# PIC.net
KiCad netlist of a schematic drawn in Altium Designer
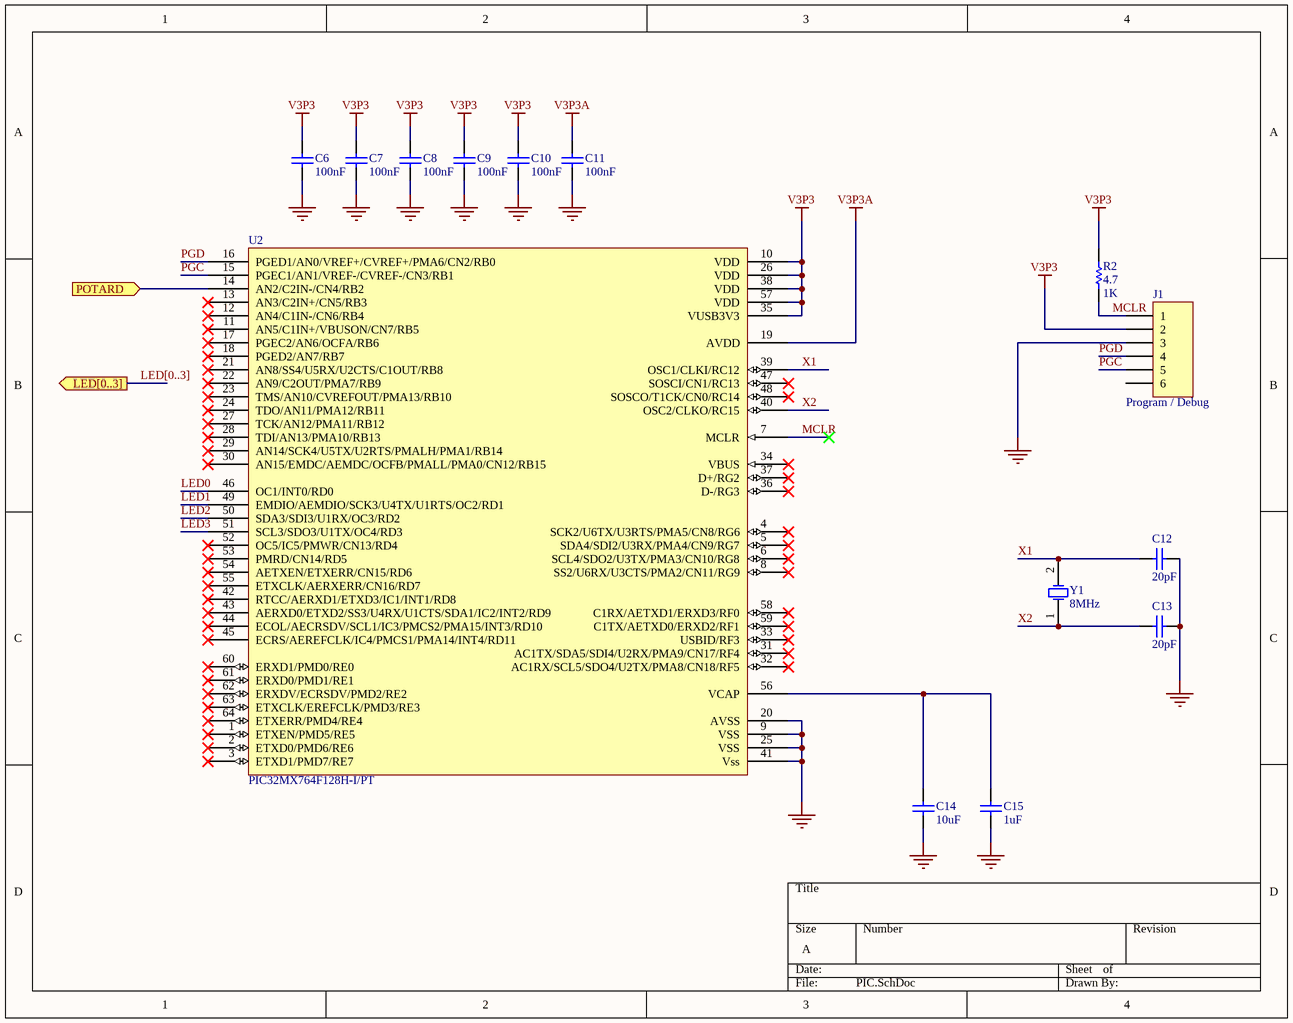
[diagram p0: PIC.SchDoc]

(export (version "E")
  (design (tool "Eeschema 10.0.6"))
  (components
    (comp (ref "C6")
      (value "100nF")
      (footprint "CAPC1608N")
      (description "Capacitor")
      (fields (field (name "PUBLISHER") "Altium Limited"))
      (libsource (lib "Miscellaneous Devices") (part "Cap"))
    )
    (comp (ref "C7")
      (value "100nF")
      (footprint "CAPC1608N")
      (description "Capacitor")
      (fields (field (name "PUBLISHER") "Altium Limited"))
      (libsource (lib "Miscellaneous Devices") (part "Cap"))
    )
    (comp (ref "C8")
      (value "100nF")
      (footprint "CAPC1608N")
      (description "Capacitor")
      (fields (field (name "PUBLISHER") "Altium Limited"))
      (libsource (lib "Miscellaneous Devices") (part "Cap"))
    )
    (comp (ref "C9")
      (value "100nF")
      (footprint "CAPC2012N")
      (description "Capacitor")
      (fields (field (name "PUBLISHER") "Altium Limited"))
      (libsource (lib "Miscellaneous Devices") (part "Cap"))
    )
    (comp (ref "C10")
      (value "100nF")
      (footprint "CAPC1608N")
      (description "Capacitor")
      (fields (field (name "PUBLISHER") "Altium Limited"))
      (libsource (lib "Miscellaneous Devices") (part "Cap"))
    )
    (comp (ref "C11")
      (value "100nF")
      (footprint "CAPC2012N")
      (description "Capacitor")
      (fields (field (name "PUBLISHER") "Altium Limited"))
      (libsource (lib "Miscellaneous Devices") (part "Cap"))
    )
    (comp (ref "C12")
      (value "20pF")
      (footprint "CAPC2012N")
      (description "Capacitor")
      (fields (field (name "PUBLISHER") "Altium Limited"))
      (libsource (lib "Miscellaneous Devices") (part "Cap"))
    )
    (comp (ref "C13")
      (value "20pF")
      (footprint "CAPC2012N")
      (description "Capacitor")
      (fields (field (name "PUBLISHER") "Altium Limited"))
      (libsource (lib "Miscellaneous Devices") (part "Cap"))
    )
    (comp (ref "C14")
      (value "10uF")
      (footprint "CAPC1608N")
      (description "Capacitor")
      (fields (field (name "PUBLISHER") "Altium Limited"))
      (libsource (lib "Miscellaneous Devices") (part "Cap"))
    )
    (comp (ref "C15")
      (value "1uF")
      (footprint "CAPC1608N")
      (description "Capacitor")
      (fields (field (name "PUBLISHER") "Altium Limited"))
      (libsource (lib "Miscellaneous Devices") (part "Cap"))
    )
    (comp (ref "J1")
      (value "Program / Debug")
      (footprint "RJ12_90")
      (description "Header, 6-Pin")
      (fields (field (name "PUBLISHER") "Altium Limited"))
      (libsource (lib "Miscellaneous Connectors") (part "Header 6"))
    )
    (comp (ref "R2")
      (value "4.7")
      (footprint "RESC1608N")
      (description "Resistor")
      (fields (field (name "ALTIUM_VALUE") "1K") (field (name "PUBLISHER") "Altium Limited"))
      (libsource (lib "Miscellaneous Devices") (part "Res1"))
    )
    (comp (ref "U2")
      (value "PIC32MX764F128H-I/PT")
      (footprint "QFP50P1200X1200X120-64")
      (libsource (lib "tp2") (part "PIC32MX764F128H-I/PT"))
    )
    (comp (ref "Y1")
      (value "8MHz")
      (footprint "HC49/4H SMX CRYSTAL")
      (description "Crystal Oscillator")
      (fields (field (name "PUBLISHER") "Altium Limited"))
      (libsource (lib "Miscellaneous Devices") (part "XTAL"))
    )
  )
  (nets
    (net (code "1") (name "/LED0") (class "Default")
      (node (ref "U2") (pin "46") (pinfunction "OC1/INT0/RD0_46") (pintype "passive"))
    )
    (net (code "2") (name "/LED1") (class "Default")
      (node (ref "U2") (pin "49") (pinfunction "EMDIO/AEMDIO/SCK3/U4TX/U1RTS/OC2/RD1_49") (pintype "passive"))
    )
    (net (code "3") (name "/LED2") (class "Default")
      (node (ref "U2") (pin "50") (pinfunction "SDA3/SDI3/U1RX/OC3/RD2_50") (pintype "passive"))
    )
    (net (code "4") (name "/LED3") (class "Default")
      (node (ref "U2") (pin "51") (pinfunction "SCL3/SDO3/U1TX/OC4/RD3_51") (pintype "passive"))
    )
    (net (code "6") (name "/MCLR") (class "Default")
      (node (ref "J1") (pin "1") (pinfunction "1_1") (pintype "passive"))
      (node (ref "R2") (pin "1") (pinfunction "1_1") (pintype "passive"))
      (node (ref "U2") (pin "7") (pinfunction "MCLR_7") (pintype "input"))
    )
    (net (code "7") (name "/PGC") (class "Default")
      (node (ref "J1") (pin "5") (pinfunction "5_5") (pintype "passive"))
      (node (ref "U2") (pin "15") (pinfunction "PGEC1/AN1/VREF-/CVREF-/CN3/RB1_15") (pintype "passive"))
    )
    (net (code "8") (name "/PGD") (class "Default")
      (node (ref "J1") (pin "4") (pinfunction "4_4") (pintype "passive"))
      (node (ref "U2") (pin "16") (pinfunction "PGED1/AN0/VREF+/CVREF+/PMA6/CN2/RB0_16") (pintype "passive"))
    )
    (net (code "9") (name "/POTARD") (class "Default")
      (node (ref "U2") (pin "14") (pinfunction "AN2/C2IN-/CN4/RB2_14") (pintype "passive"))
    )
    (net (code "10") (name "/X1") (class "Default")
      (node (ref "C12") (pin "2") (pinfunction "2_2") (pintype "passive"))
      (node (ref "U2") (pin "39") (pinfunction "OSC1/CLKI/RC12_39") (pintype "bidirectional"))
      (node (ref "Y1") (pin "2") (pinfunction "OSC2_2") (pintype "passive"))
    )
    (net (code "11") (name "/X2") (class "Default")
      (node (ref "C13") (pin "2") (pinfunction "2_2") (pintype "passive"))
      (node (ref "U2") (pin "40") (pinfunction "OSC2/CLKO/RC15_40") (pintype "bidirectional"))
      (node (ref "Y1") (pin "1") (pinfunction "OSC1_1") (pintype "passive"))
    )
    (net (code "12") (name "GND") (class "Default")
      (node (ref "C10") (pin "1") (pinfunction "1_1") (pintype "passive"))
      (node (ref "C11") (pin "1") (pinfunction "1_1") (pintype "passive"))
      (node (ref "C12") (pin "1") (pinfunction "1_1") (pintype "passive"))
      (node (ref "C13") (pin "1") (pinfunction "1_1") (pintype "passive"))
      (node (ref "C14") (pin "1") (pinfunction "1_1") (pintype "passive"))
      (node (ref "C15") (pin "1") (pinfunction "1_1") (pintype "passive"))
      (node (ref "C6") (pin "1") (pinfunction "1_1") (pintype "passive"))
      (node (ref "C7") (pin "1") (pinfunction "1_1") (pintype "passive"))
      (node (ref "C8") (pin "1") (pinfunction "1_1") (pintype "passive"))
      (node (ref "C9") (pin "1") (pinfunction "1_1") (pintype "passive"))
      (node (ref "J1") (pin "3") (pinfunction "3_3") (pintype "passive"))
      (node (ref "U2") (pin "20") (pinfunction "AVSS_20") (pintype "power_in"))
      (node (ref "U2") (pin "25") (pinfunction "VSS_25") (pintype "power_in"))
      (node (ref "U2") (pin "41") (pinfunction "Vss_41") (pintype "power_in"))
      (node (ref "U2") (pin "9") (pinfunction "VSS_9") (pintype "power_in"))
    )
    (net (code "13") (name "Net-(U2-VCAP)") (class "Default")
      (node (ref "C14") (pin "2") (pinfunction "2_2") (pintype "passive"))
      (node (ref "C15") (pin "2") (pinfunction "2_2") (pintype "passive"))
      (node (ref "U2") (pin "56") (pinfunction "VCAP_56") (pintype "power_in"))
    )
    (net (code "14") (name "V3P3") (class "Default")
      (node (ref "C10") (pin "2") (pinfunction "2_2") (pintype "passive"))
      (node (ref "C6") (pin "2") (pinfunction "2_2") (pintype "passive"))
      (node (ref "C7") (pin "2") (pinfunction "2_2") (pintype "passive"))
      (node (ref "C8") (pin "2") (pinfunction "2_2") (pintype "passive"))
      (node (ref "C9") (pin "2") (pinfunction "2_2") (pintype "passive"))
      (node (ref "J1") (pin "2") (pinfunction "2_2") (pintype "passive"))
      (node (ref "R2") (pin "2") (pinfunction "2_2") (pintype "passive"))
      (node (ref "U2") (pin "10") (pinfunction "VDD_10") (pintype "power_in"))
      (node (ref "U2") (pin "26") (pinfunction "VDD_26") (pintype "power_in"))
      (node (ref "U2") (pin "35") (pinfunction "VUSB3V3_35") (pintype "power_in"))
      (node (ref "U2") (pin "38") (pinfunction "VDD_38") (pintype "power_in"))
      (node (ref "U2") (pin "57") (pinfunction "VDD_57") (pintype "power_in"))
    )
    (net (code "15") (name "V3P3A") (class "Default")
      (node (ref "C11") (pin "2") (pinfunction "2_2") (pintype "passive"))
      (node (ref "U2") (pin "19") (pinfunction "AVDD_19") (pintype "power_in"))
    )
    (net (code "16") (name "unconnected-(J1-Pad6)") (class "Default")
      (node (ref "J1") (pin "6") (pinfunction "6_6") (pintype "passive"))
    )
    (net (code "17") (name "unconnected-(U2-AC1RX{slash}SCL5{slash}SDO4{slash}U2TX{slash}PMA8{slash}CN18{slash}RF5-Pad32)") (class "Default")
      (node (ref "U2") (pin "32") (pinfunction "AC1RX/SCL5/SDO4/U2TX/PMA8/CN18/RF5_32") (pintype "bidirectional+no_connect"))
    )
    (net (code "18") (name "unconnected-(U2-AC1TX{slash}SDA5{slash}SDI4{slash}U2RX{slash}PMA9{slash}CN17{slash}RF4-Pad31)") (class "Default")
      (node (ref "U2") (pin "31") (pinfunction "AC1TX/SDA5/SDI4/U2RX/PMA9/CN17/RF4_31") (pintype "bidirectional+no_connect"))
    )
    (net (code "19") (name "unconnected-(U2-AERXD0{slash}ETXD2{slash}SS3{slash}U4RX{slash}U1CTS{slash}SDA1{slash}IC2{slash}INT2{slash}RD9-Pad43)") (class "Default")
      (node (ref "U2") (pin "43") (pinfunction "AERXD0/ETXD2/SS3/U4RX/U1CTS/SDA1/IC2/INT2/RD9_43") (pintype "passive+no_connect"))
    )
    (net (code "20") (name "unconnected-(U2-AETXEN{slash}ETXERR{slash}CN15{slash}RD6-Pad54)") (class "Default")
      (node (ref "U2") (pin "54") (pinfunction "AETXEN/ETXERR/CN15/RD6_54") (pintype "passive+no_connect"))
    )
    (net (code "21") (name "unconnected-(U2-AN3{slash}C2IN+{slash}CN5{slash}RB3-Pad13)") (class "Default")
      (node (ref "U2") (pin "13") (pinfunction "AN3/C2IN+/CN5/RB3_13") (pintype "passive+no_connect"))
    )
    (net (code "22") (name "unconnected-(U2-AN4{slash}C1IN-{slash}CN6{slash}RB4-Pad12)") (class "Default")
      (node (ref "U2") (pin "12") (pinfunction "AN4/C1IN-/CN6/RB4_12") (pintype "passive+no_connect"))
    )
    (net (code "23") (name "unconnected-(U2-AN5{slash}C1IN+{slash}VBUSON{slash}CN7{slash}RB5-Pad11)") (class "Default")
      (node (ref "U2") (pin "11") (pinfunction "AN5/C1IN+/VBUSON/CN7/RB5_11") (pintype "passive+no_connect"))
    )
    (net (code "24") (name "unconnected-(U2-AN8{slash}SS4{slash}U5RX{slash}U2CTS{slash}C1OUT{slash}RB8-Pad21)") (class "Default")
      (node (ref "U2") (pin "21") (pinfunction "AN8/SS4/U5RX/U2CTS/C1OUT/RB8_21") (pintype "passive+no_connect"))
    )
    (net (code "25") (name "unconnected-(U2-AN9{slash}C2OUT{slash}PMA7{slash}RB9-Pad22)") (class "Default")
      (node (ref "U2") (pin "22") (pinfunction "AN9/C2OUT/PMA7/RB9_22") (pintype "passive+no_connect"))
    )
    (net (code "26") (name "unconnected-(U2-AN14{slash}SCK4{slash}U5TX{slash}U2RTS{slash}PMALH{slash}PMA1{slash}RB14-Pad29)") (class "Default")
      (node (ref "U2") (pin "29") (pinfunction "AN14/SCK4/U5TX/U2RTS/PMALH/PMA1/RB14_29") (pintype "passive+no_connect"))
    )
    (net (code "27") (name "unconnected-(U2-AN15{slash}EMDC{slash}AEMDC{slash}OCFB{slash}PMALL{slash}PMA0{slash}CN12{slash}RB15-Pad30)") (class "Default")
      (node (ref "U2") (pin "30") (pinfunction "AN15/EMDC/AEMDC/OCFB/PMALL/PMA0/CN12/RB15_30") (pintype "passive+no_connect"))
    )
    (net (code "28") (name "unconnected-(U2-C1RX{slash}AETXD1{slash}ERXD3{slash}RF0-Pad58)") (class "Default")
      (node (ref "U2") (pin "58") (pinfunction "C1RX/AETXD1/ERXD3/RF0_58") (pintype "bidirectional+no_connect"))
    )
    (net (code "29") (name "unconnected-(U2-C1TX{slash}AETXD0{slash}ERXD2{slash}RF1-Pad59)") (class "Default")
      (node (ref "U2") (pin "59") (pinfunction "C1TX/AETXD0/ERXD2/RF1_59") (pintype "bidirectional+no_connect"))
    )
    (net (code "30") (name "unconnected-(U2-D+{slash}RG2-Pad37)") (class "Default")
      (node (ref "U2") (pin "37") (pinfunction "D+/RG2_37") (pintype "bidirectional+no_connect"))
    )
    (net (code "31") (name "unconnected-(U2-D-{slash}RG3-Pad36)") (class "Default")
      (node (ref "U2") (pin "36") (pinfunction "D-/RG3_36") (pintype "bidirectional+no_connect"))
    )
    (net (code "32") (name "unconnected-(U2-ECOL{slash}AECRSDV{slash}SCL1{slash}IC3{slash}PMCS2{slash}PMA15{slash}INT3{slash}RD10-Pad44)") (class "Default")
      (node (ref "U2") (pin "44") (pinfunction "ECOL/AECRSDV/SCL1/IC3/PMCS2/PMA15/INT3/RD10_44") (pintype "passive+no_connect"))
    )
    (net (code "33") (name "unconnected-(U2-ECRS{slash}AEREFCLK{slash}IC4{slash}PMCS1{slash}PMA14{slash}INT4{slash}RD11-Pad45)") (class "Default")
      (node (ref "U2") (pin "45") (pinfunction "ECRS/AEREFCLK/IC4/PMCS1/PMA14/INT4/RD11_45") (pintype "passive+no_connect"))
    )
    (net (code "34") (name "unconnected-(U2-ERXD0{slash}PMD1{slash}RE1-Pad61)") (class "Default")
      (node (ref "U2") (pin "61") (pinfunction "ERXD0/PMD1/RE1_61") (pintype "bidirectional+no_connect"))
    )
    (net (code "35") (name "unconnected-(U2-ERXD1{slash}PMD0{slash}RE0-Pad60)") (class "Default")
      (node (ref "U2") (pin "60") (pinfunction "ERXD1/PMD0/RE0_60") (pintype "bidirectional+no_connect"))
    )
    (net (code "36") (name "unconnected-(U2-ERXDV{slash}ECRSDV{slash}PMD2{slash}RE2-Pad62)") (class "Default")
      (node (ref "U2") (pin "62") (pinfunction "ERXDV/ECRSDV/PMD2/RE2_62") (pintype "bidirectional+no_connect"))
    )
    (net (code "37") (name "unconnected-(U2-ETXCLK{slash}AERXERR{slash}CN16{slash}RD7-Pad55)") (class "Default")
      (node (ref "U2") (pin "55") (pinfunction "ETXCLK/AERXERR/CN16/RD7_55") (pintype "passive+no_connect"))
    )
    (net (code "38") (name "unconnected-(U2-ETXCLK{slash}EREFCLK{slash}PMD3{slash}RE3-Pad63)") (class "Default")
      (node (ref "U2") (pin "63") (pinfunction "ETXCLK/EREFCLK/PMD3/RE3_63") (pintype "bidirectional+no_connect"))
    )
    (net (code "39") (name "unconnected-(U2-ETXD0{slash}PMD6{slash}RE6-Pad2)") (class "Default")
      (node (ref "U2") (pin "2") (pinfunction "ETXD0/PMD6/RE6_2") (pintype "bidirectional+no_connect"))
    )
    (net (code "40") (name "unconnected-(U2-ETXD1{slash}PMD7{slash}RE7-Pad3)") (class "Default")
      (node (ref "U2") (pin "3") (pinfunction "ETXD1/PMD7/RE7_3") (pintype "bidirectional+no_connect"))
    )
    (net (code "41") (name "unconnected-(U2-ETXEN{slash}PMD5{slash}RE5-Pad1)") (class "Default")
      (node (ref "U2") (pin "1") (pinfunction "ETXEN/PMD5/RE5_1") (pintype "bidirectional+no_connect"))
    )
    (net (code "42") (name "unconnected-(U2-ETXERR{slash}PMD4{slash}RE4-Pad64)") (class "Default")
      (node (ref "U2") (pin "64") (pinfunction "ETXERR/PMD4/RE4_64") (pintype "bidirectional+no_connect"))
    )
    (net (code "43") (name "unconnected-(U2-OC5{slash}IC5{slash}PMWR{slash}CN13{slash}RD4-Pad52)") (class "Default")
      (node (ref "U2") (pin "52") (pinfunction "OC5/IC5/PMWR/CN13/RD4_52") (pintype "passive+no_connect"))
    )
    (net (code "44") (name "unconnected-(U2-PGEC2{slash}AN6{slash}OCFA{slash}RB6-Pad17)") (class "Default")
      (node (ref "U2") (pin "17") (pinfunction "PGEC2/AN6/OCFA/RB6_17") (pintype "passive+no_connect"))
    )
    (net (code "45") (name "unconnected-(U2-PGED2{slash}AN7{slash}RB7-Pad18)") (class "Default")
      (node (ref "U2") (pin "18") (pinfunction "PGED2/AN7/RB7_18") (pintype "passive+no_connect"))
    )
    (net (code "46") (name "unconnected-(U2-PMRD{slash}CN14{slash}RD5-Pad53)") (class "Default")
      (node (ref "U2") (pin "53") (pinfunction "PMRD/CN14/RD5_53") (pintype "passive+no_connect"))
    )
    (net (code "47") (name "unconnected-(U2-RTCC{slash}AERXD1{slash}ETXD3{slash}IC1{slash}INT1{slash}RD8-Pad42)") (class "Default")
      (node (ref "U2") (pin "42") (pinfunction "RTCC/AERXD1/ETXD3/IC1/INT1/RD8_42") (pintype "passive+no_connect"))
    )
    (net (code "48") (name "unconnected-(U2-SCK2{slash}U6TX{slash}U3RTS{slash}PMA5{slash}CN8{slash}RG6-Pad4)") (class "Default")
      (node (ref "U2") (pin "4") (pinfunction "SCK2/U6TX/U3RTS/PMA5/CN8/RG6_4") (pintype "bidirectional+no_connect"))
    )
    (net (code "49") (name "unconnected-(U2-SCL4{slash}SDO2{slash}U3TX{slash}PMA3{slash}CN10{slash}RG8-Pad6)") (class "Default")
      (node (ref "U2") (pin "6") (pinfunction "SCL4/SDO2/U3TX/PMA3/CN10/RG8_6") (pintype "bidirectional+no_connect"))
    )
    (net (code "50") (name "unconnected-(U2-SDA4{slash}SDI2{slash}U3RX{slash}PMA4{slash}CN9{slash}RG7-Pad5)") (class "Default")
      (node (ref "U2") (pin "5") (pinfunction "SDA4/SDI2/U3RX/PMA4/CN9/RG7_5") (pintype "bidirectional+no_connect"))
    )
    (net (code "51") (name "unconnected-(U2-SOSCI{slash}CN1{slash}RC13-Pad47)") (class "Default")
      (node (ref "U2") (pin "47") (pinfunction "SOSCI/CN1/RC13_47") (pintype "bidirectional+no_connect"))
    )
    (net (code "52") (name "unconnected-(U2-SOSCO{slash}T1CK{slash}CN0{slash}RC14-Pad48)") (class "Default")
      (node (ref "U2") (pin "48") (pinfunction "SOSCO/T1CK/CN0/RC14_48") (pintype "bidirectional+no_connect"))
    )
    (net (code "53") (name "unconnected-(U2-SS2{slash}U6RX{slash}U3CTS{slash}PMA2{slash}CN11{slash}RG9-Pad8)") (class "Default")
      (node (ref "U2") (pin "8") (pinfunction "SS2/U6RX/U3CTS/PMA2/CN11/RG9_8") (pintype "bidirectional+no_connect"))
    )
    (net (code "54") (name "unconnected-(U2-TCK{slash}AN12{slash}PMA11{slash}RB12-Pad27)") (class "Default")
      (node (ref "U2") (pin "27") (pinfunction "TCK/AN12/PMA11/RB12_27") (pintype "passive+no_connect"))
    )
    (net (code "55") (name "unconnected-(U2-TDI{slash}AN13{slash}PMA10{slash}RB13-Pad28)") (class "Default")
      (node (ref "U2") (pin "28") (pinfunction "TDI/AN13/PMA10/RB13_28") (pintype "passive+no_connect"))
    )
    (net (code "56") (name "unconnected-(U2-TDO{slash}AN11{slash}PMA12{slash}RB11-Pad24)") (class "Default")
      (node (ref "U2") (pin "24") (pinfunction "TDO/AN11/PMA12/RB11_24") (pintype "passive+no_connect"))
    )
    (net (code "57") (name "unconnected-(U2-TMS{slash}AN10{slash}CVREFOUT{slash}PMA13{slash}RB10-Pad23)") (class "Default")
      (node (ref "U2") (pin "23") (pinfunction "TMS/AN10/CVREFOUT/PMA13/RB10_23") (pintype "passive+no_connect"))
    )
    (net (code "58") (name "unconnected-(U2-USBID{slash}RF3-Pad33)") (class "Default")
      (node (ref "U2") (pin "33") (pinfunction "USBID/RF3_33") (pintype "bidirectional+no_connect"))
    )
    (net (code "59") (name "unconnected-(U2-VBUS-Pad34)") (class "Default")
      (node (ref "U2") (pin "34") (pinfunction "VBUS_34") (pintype "input+no_connect"))
    )
  )
)
